# RPi_RFM12B_ISP_v1_1.net
KiCad netlist of a schematic drawn in EAGLE
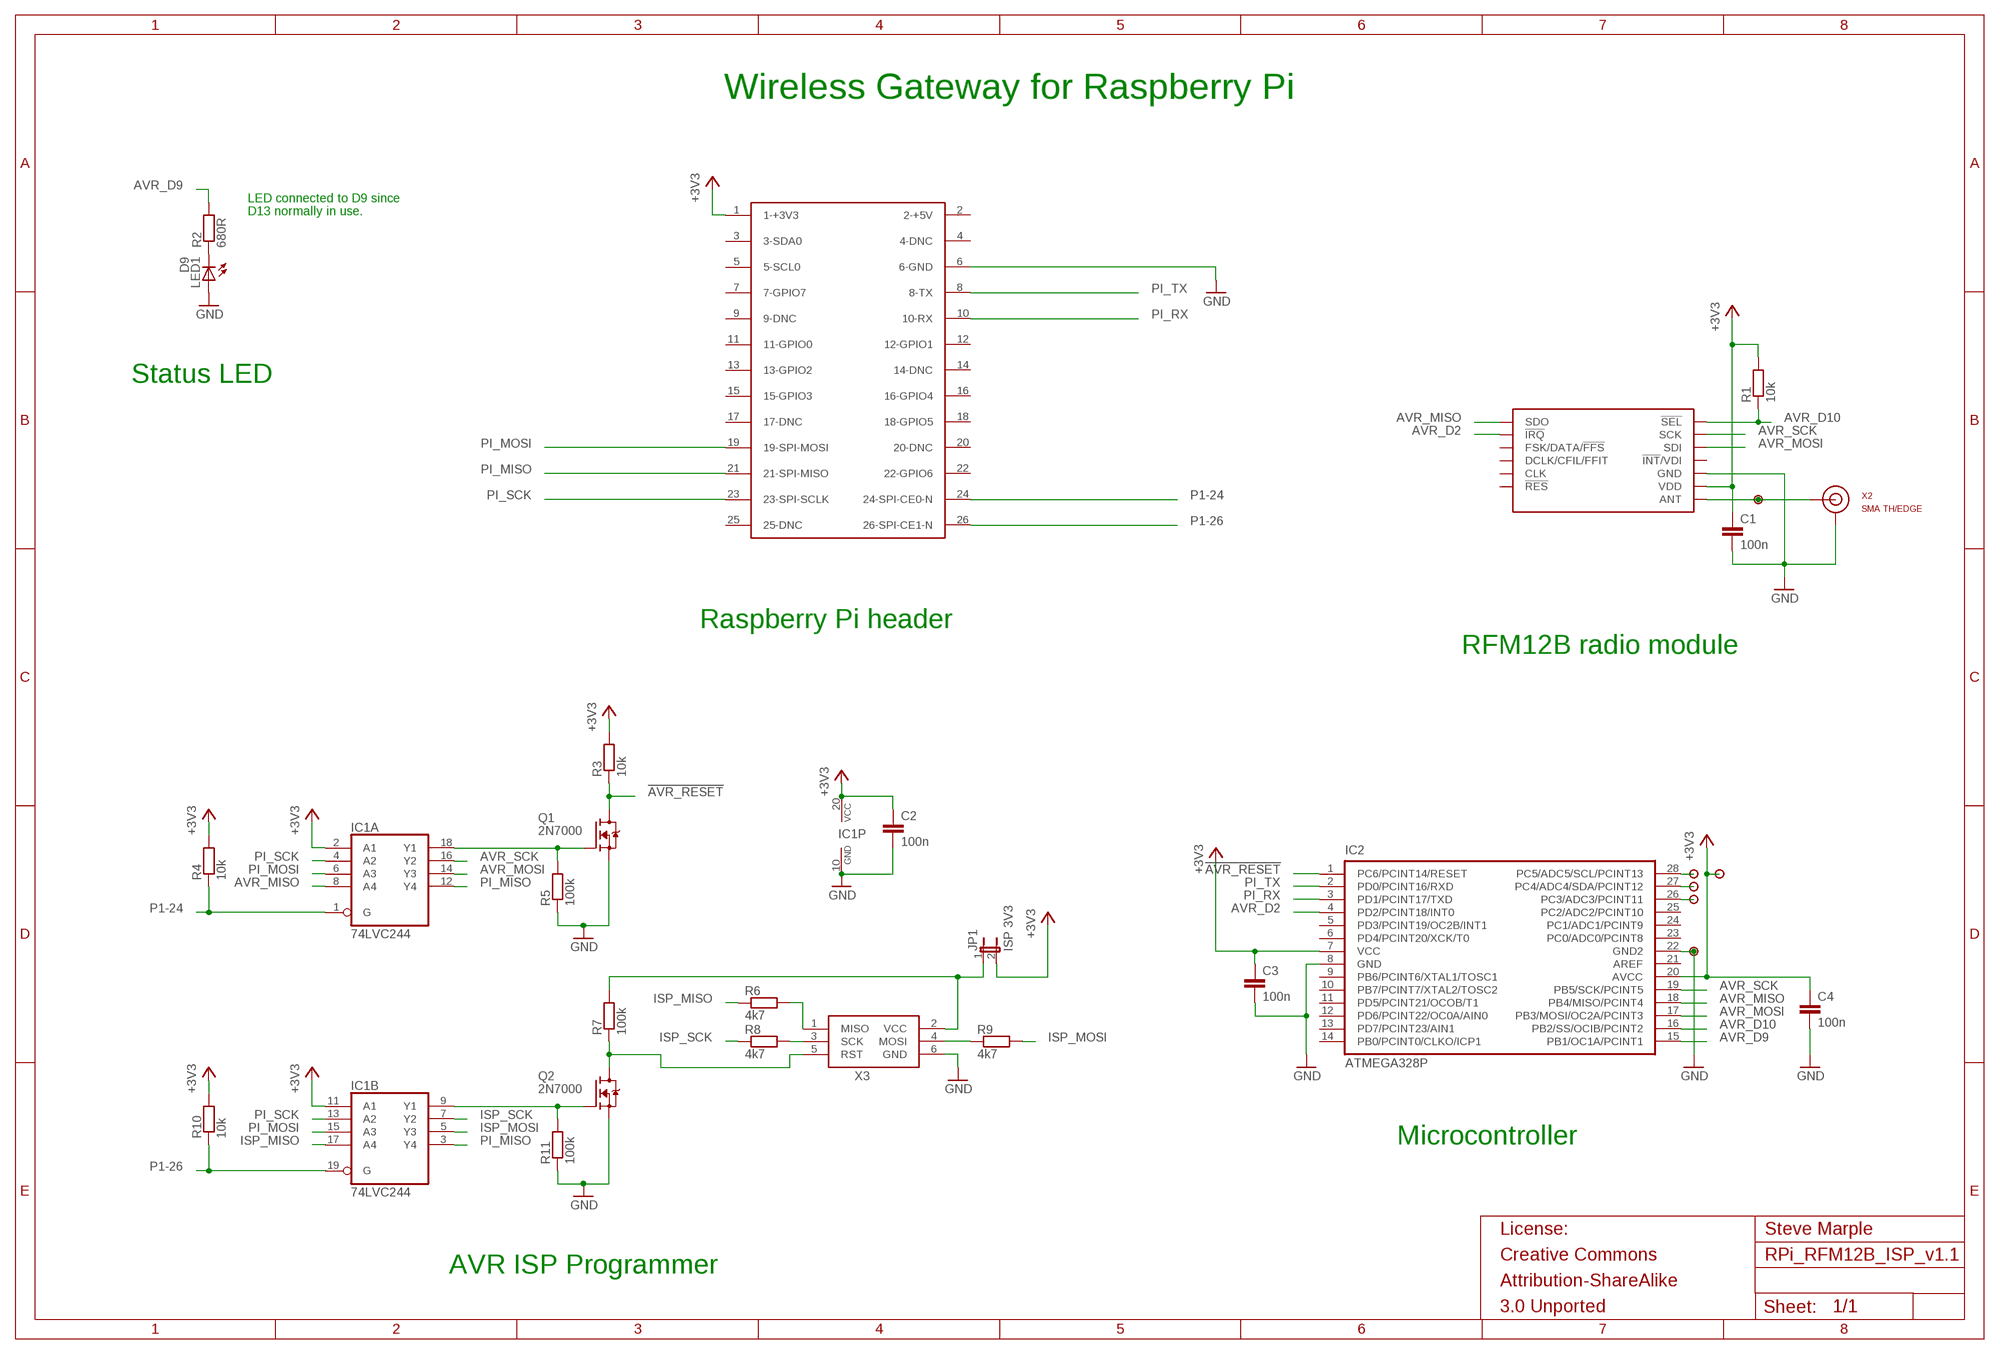
[diagram p0: schematic, sheet 1]

(export (version "E")
  (design (tool "Eeschema 10.0.6"))
  (components
    (comp (ref "AVR_A1")
      (value "PAD")
      (footprint "eagle-import:PAD")
      (libsource (lib "eagle-import") (part "PAD"))
    )
    (comp (ref "AVR_A2")
      (value "PAD")
      (footprint "eagle-import:PAD")
      (libsource (lib "eagle-import") (part "PAD"))
    )
    (comp (ref "AVR_A3")
      (value "PAD")
      (footprint "eagle-import:PAD")
      (libsource (lib "eagle-import") (part "PAD"))
    )
    (comp (ref "AVR_A4")
      (value "PAD")
      (footprint "eagle-import:PAD")
      (libsource (lib "eagle-import") (part "PAD"))
    )
    (comp (ref "AVR_A5")
      (value "PAD")
      (footprint "eagle-import:PAD")
      (libsource (lib "eagle-import") (part "PAD"))
    )
    (comp (ref "C1")
      (value "100n")
      (footprint "eagle-import:CAP-PTH-SMALL")
      (libsource (lib "eagle-import") (part "CAPPTH"))
    )
    (comp (ref "C2")
      (value "100n")
      (footprint "eagle-import:CAP-PTH-SMALL")
      (libsource (lib "eagle-import") (part "CAPPTH"))
    )
    (comp (ref "C3")
      (value "100n")
      (footprint "eagle-import:CAP-PTH-SMALL")
      (libsource (lib "eagle-import") (part "CAPPTH"))
    )
    (comp (ref "C4")
      (value "100n")
      (footprint "eagle-import:CAP-PTH-SMALL")
      (libsource (lib "eagle-import") (part "CAPPTH"))
    )
    (comp (ref "IC1")
      (value "74LVC244")
      (footprint "eagle-import:DIL20")
      (libsource (lib "eagle-import") (part "74244NHC"))
    )
    (comp (ref "IC2")
      (value "ATMEGA328P")
      (footprint "eagle-import:DIL28-N")
      (libsource (lib "eagle-import") (part "IC_UC_ATMEGA328PDIL"))
    )
    (comp (ref "JP1")
      (value "ISP 3V3")
      (footprint "eagle-import:1X02")
      (libsource (lib "eagle-import") (part "JUMPER-2PTH"))
    )
    (comp (ref "LED1")
      (value "D9")
      (footprint "eagle-import:LED3MM")
      (libsource (lib "eagle-import") (part "LED3MM"))
    )
    (comp (ref "Q1")
      (value "2N7000")
      (footprint "eagle-import:TO-92")
      (libsource (lib "eagle-import") (part "2N7000"))
    )
    (comp (ref "Q2")
      (value "2N7000")
      (footprint "eagle-import:TO-92")
      (libsource (lib "eagle-import") (part "2N7000"))
    )
    (comp (ref "R1")
      (value "10k")
      (footprint "eagle-import:RES-AXIAL-0.4")
      (libsource (lib "eagle-import") (part "RESISTOR"))
    )
    (comp (ref "R2")
      (value "680R")
      (footprint "eagle-import:RES-AXIAL-0.4")
      (libsource (lib "eagle-import") (part "RESISTOR"))
    )
    (comp (ref "R3")
      (value "10k")
      (footprint "eagle-import:RES-AXIAL-0.4")
      (libsource (lib "eagle-import") (part "RESISTOR"))
    )
    (comp (ref "R4")
      (value "10k")
      (footprint "eagle-import:RES-AXIAL-0.4")
      (libsource (lib "eagle-import") (part "RESISTOR"))
    )
    (comp (ref "R5")
      (value "100k")
      (footprint "eagle-import:RES-AXIAL-0.4")
      (libsource (lib "eagle-import") (part "RESISTOR"))
    )
    (comp (ref "R6")
      (value "4k7")
      (footprint "eagle-import:RES-AXIAL-0.4")
      (libsource (lib "eagle-import") (part "RESISTOR"))
    )
    (comp (ref "R7")
      (value "100k")
      (footprint "eagle-import:RES-AXIAL-0.4")
      (libsource (lib "eagle-import") (part "RESISTOR"))
    )
    (comp (ref "R8")
      (value "4k7")
      (footprint "eagle-import:RES-AXIAL-0.4")
      (libsource (lib "eagle-import") (part "RESISTOR"))
    )
    (comp (ref "R9")
      (value "4k7")
      (footprint "eagle-import:RES-AXIAL-0.4")
      (libsource (lib "eagle-import") (part "RESISTOR"))
    )
    (comp (ref "R10")
      (value "10k")
      (footprint "eagle-import:RES-AXIAL-0.4")
      (libsource (lib "eagle-import") (part "RESISTOR"))
    )
    (comp (ref "R11")
      (value "100k")
      (footprint "eagle-import:RES-AXIAL-0.4")
      (libsource (lib "eagle-import") (part "RESISTOR"))
    )
    (comp (ref "RF1")
      (value "RFM12B")
      (footprint "eagle-import:RFM12B")
      (libsource (lib "eagle-import") (part "RFM12BSMD"))
    )
    (comp (ref "RFM12B_ANT")
      (value "PAD")
      (footprint "eagle-import:PAD")
      (libsource (lib "eagle-import") (part "PAD"))
    )
    (comp (ref "X1")
      (value "P1A")
      (footprint "eagle-import:RASPBERRY-PI-HEADER")
      (libsource (lib "eagle-import") (part "RASPBERRY-PIHEADER"))
    )
    (comp (ref "X2")
      (value "SMA TH/EDGE")
      (footprint "eagle-import:SMA-THD-EDGE")
      (libsource (lib "eagle-import") (part "CONN-SMATHD-SMD-EDGE"))
    )
    (comp (ref "X3")
      (value "AVR ISP")
      (footprint "eagle-import:CONN-HARTING-ML6")
      (libsource (lib "eagle-import") (part "AVRISP-HEADER-6-SHROUDED"))
    )
  )
  (nets
    (net (code "1") (name "+3V3") (class "Default")
      (node (ref "AVR_A5") (pin "1") (pinfunction "1_1") (pintype "bidirectional"))
      (node (ref "C1") (pin "1") (pinfunction "1_1") (pintype "passive"))
      (node (ref "C2") (pin "1") (pinfunction "1_1") (pintype "passive"))
      (node (ref "C3") (pin "1") (pinfunction "1_1") (pintype "passive"))
      (node (ref "C4") (pin "1") (pinfunction "1_1") (pintype "passive"))
      (node (ref "IC1") (pin "11") (pinfunction "A1_11") (pintype "input"))
      (node (ref "IC1") (pin "2") (pinfunction "A1_2") (pintype "input"))
      (node (ref "IC1") (pin "20") (pinfunction "VCC_20") (pintype "power_in"))
      (node (ref "IC2") (pin "20") (pinfunction "AVCC_20") (pintype "bidirectional"))
      (node (ref "IC2") (pin "7") (pinfunction "VCC_7") (pintype "bidirectional"))
      (node (ref "JP1") (pin "2") (pinfunction "2_2") (pintype "passive"))
      (node (ref "R1") (pin "P$2") (pinfunction "2_P$2") (pintype "passive"))
      (node (ref "R10") (pin "P$2") (pinfunction "2_P$2") (pintype "passive"))
      (node (ref "R3") (pin "P$2") (pinfunction "2_P$2") (pintype "passive"))
      (node (ref "R4") (pin "P$2") (pinfunction "2_P$2") (pintype "passive"))
      (node (ref "RF1") (pin "VDD") (pinfunction "VDD_VDD") (pintype "power_in"))
      (node (ref "X1") (pin "1") (pinfunction "1-+3V3_1") (pintype "bidirectional"))
    )
    (net (code "2") (name "/AVR_D2") (class "Default")
      (node (ref "IC2") (pin "4") (pinfunction "PD2/PCINT18/INT0_4") (pintype "bidirectional"))
      (node (ref "RF1") (pin "!IRQ") (pinfunction "~{IRQ}_!IRQ") (pintype "output"))
    )
    (net (code "3") (name "/AVR_D9") (class "Default")
      (node (ref "IC2") (pin "15") (pinfunction "PB1/OC1A/PCINT1_15") (pintype "bidirectional"))
      (node (ref "R2") (pin "P$2") (pinfunction "2_P$2") (pintype "passive"))
    )
    (net (code "4") (name "/AVR_D10") (class "Default")
      (node (ref "IC2") (pin "16") (pinfunction "PB2/SS/OCIB/PCINT2_16") (pintype "bidirectional"))
      (node (ref "R1") (pin "P$1") (pinfunction "1_P$1") (pintype "passive"))
      (node (ref "RF1") (pin "!SEL") (pinfunction "~{SEL}_!SEL") (pintype "input"))
    )
    (net (code "5") (name "/AVR_MISO") (class "Default")
      (node (ref "IC1") (pin "8") (pinfunction "A4_8") (pintype "input"))
      (node (ref "IC2") (pin "18") (pinfunction "PB4/MISO/PCINT4_18") (pintype "bidirectional"))
      (node (ref "RF1") (pin "SDO") (pinfunction "SDO_SDO") (pintype "output"))
    )
    (net (code "6") (name "/AVR_MOSI") (class "Default")
      (node (ref "IC1") (pin "14") (pinfunction "Y3_14") (pintype "tri_state"))
      (node (ref "IC2") (pin "17") (pinfunction "PB3/MOSI/OC2A/PCINT3_17") (pintype "bidirectional"))
      (node (ref "RF1") (pin "SDI") (pinfunction "SDI_SDI") (pintype "input"))
    )
    (net (code "7") (name "/AVR_SCK") (class "Default")
      (node (ref "IC1") (pin "16") (pinfunction "Y2_16") (pintype "tri_state"))
      (node (ref "IC2") (pin "19") (pinfunction "PB5/SCK/PCINT5_19") (pintype "bidirectional"))
      (node (ref "RF1") (pin "SCK") (pinfunction "SCK_SCK") (pintype "input"))
    )
    (net (code "8") (name "/ISP_MISO") (class "Default")
      (node (ref "IC1") (pin "17") (pinfunction "A4_17") (pintype "input"))
      (node (ref "R6") (pin "P$1") (pinfunction "1_P$1") (pintype "passive"))
    )
    (net (code "9") (name "/ISP_MOSI") (class "Default")
      (node (ref "IC1") (pin "5") (pinfunction "Y3_5") (pintype "tri_state"))
      (node (ref "R9") (pin "P$2") (pinfunction "2_P$2") (pintype "passive"))
    )
    (net (code "10") (name "/ISP_SCK") (class "Default")
      (node (ref "IC1") (pin "7") (pinfunction "Y2_7") (pintype "tri_state"))
      (node (ref "R8") (pin "P$1") (pinfunction "1_P$1") (pintype "passive"))
    )
    (net (code "11") (name "/P1-24") (class "Default")
      (node (ref "IC1") (pin "1") (pinfunction "G_1") (pintype "input"))
      (node (ref "R4") (pin "P$1") (pinfunction "1_P$1") (pintype "passive"))
      (node (ref "X1") (pin "24") (pinfunction "24-SPI-CE0-N_24") (pintype "bidirectional"))
    )
    (net (code "12") (name "/P1-26") (class "Default")
      (node (ref "IC1") (pin "19") (pinfunction "G_19") (pintype "input"))
      (node (ref "R10") (pin "P$1") (pinfunction "1_P$1") (pintype "passive"))
      (node (ref "X1") (pin "26") (pinfunction "26-SPI-CE1-N_26") (pintype "bidirectional"))
    )
    (net (code "13") (name "/PI_MISO") (class "Default")
      (node (ref "IC1") (pin "12") (pinfunction "Y4_12") (pintype "tri_state"))
      (node (ref "IC1") (pin "3") (pinfunction "Y4_3") (pintype "tri_state"))
      (node (ref "X1") (pin "21") (pinfunction "21-SPI-MISO_21") (pintype "bidirectional"))
    )
    (net (code "14") (name "/PI_MOSI") (class "Default")
      (node (ref "IC1") (pin "15") (pinfunction "A3_15") (pintype "input"))
      (node (ref "IC1") (pin "6") (pinfunction "A3_6") (pintype "input"))
      (node (ref "X1") (pin "19") (pinfunction "19-SPI-MOSI_19") (pintype "bidirectional"))
    )
    (net (code "15") (name "/PI_RX") (class "Default")
      (node (ref "IC2") (pin "3") (pinfunction "PD1/PCINT17/TXD_3") (pintype "bidirectional"))
      (node (ref "X1") (pin "10") (pinfunction "10-RX_10") (pintype "bidirectional"))
    )
    (net (code "16") (name "/PI_SCK") (class "Default")
      (node (ref "IC1") (pin "13") (pinfunction "A2_13") (pintype "input"))
      (node (ref "IC1") (pin "4") (pinfunction "A2_4") (pintype "input"))
      (node (ref "X1") (pin "23") (pinfunction "23-SPI-SCLK_23") (pintype "bidirectional"))
    )
    (net (code "17") (name "/PI_TX") (class "Default")
      (node (ref "IC2") (pin "2") (pinfunction "PD0/PCINT16/RXD_2") (pintype "bidirectional"))
      (node (ref "X1") (pin "8") (pinfunction "8-TX_8") (pintype "bidirectional"))
    )
    (net (code "18") (name "/~{AVR_RESET}") (class "Default")
      (node (ref "IC2") (pin "1") (pinfunction "PC6/PCINT14/RESET_1") (pintype "bidirectional"))
      (node (ref "Q1") (pin "3") (pinfunction "D_3") (pintype "passive"))
      (node (ref "R3") (pin "P$1") (pinfunction "1_P$1") (pintype "passive"))
    )
    (net (code "19") (name "GND") (class "Default")
      (node (ref "AVR_A4") (pin "1") (pinfunction "1_1") (pintype "bidirectional"))
      (node (ref "C1") (pin "2") (pinfunction "2_2") (pintype "passive"))
      (node (ref "C2") (pin "2") (pinfunction "2_2") (pintype "passive"))
      (node (ref "C3") (pin "2") (pinfunction "2_2") (pintype "passive"))
      (node (ref "C4") (pin "2") (pinfunction "2_2") (pintype "passive"))
      (node (ref "IC1") (pin "10") (pinfunction "GND_10") (pintype "power_in"))
      (node (ref "IC2") (pin "22") (pinfunction "GND2_22") (pintype "bidirectional"))
      (node (ref "IC2") (pin "8") (pinfunction "GND_8") (pintype "bidirectional"))
      (node (ref "LED1") (pin "A") (pinfunction "A_A") (pintype "passive"))
      (node (ref "Q1") (pin "1") (pinfunction "S_1") (pintype "passive"))
      (node (ref "Q2") (pin "1") (pinfunction "S_1") (pintype "passive"))
      (node (ref "R11") (pin "P$1") (pinfunction "1_P$1") (pintype "passive"))
      (node (ref "R5") (pin "P$1") (pinfunction "1_P$1") (pintype "passive"))
      (node (ref "RF1") (pin "GND@0") (pinfunction "GND_GND@0") (pintype "power_in"))
      (node (ref "RF1") (pin "GND@1") (pinfunction "GND_GND@1") (pintype "power_in"))
      (node (ref "X1") (pin "6") (pinfunction "6-GND_6") (pintype "bidirectional"))
      (node (ref "X2") (pin "GND@0") (pinfunction "GND_GND@0") (pintype "bidirectional"))
      (node (ref "X2") (pin "GND@1") (pinfunction "GND_GND@1") (pintype "bidirectional"))
      (node (ref "X2") (pin "GND@2") (pinfunction "GND_GND@2") (pintype "bidirectional"))
      (node (ref "X2") (pin "GND@3") (pinfunction "GND_GND@3") (pintype "bidirectional"))
      (node (ref "X2") (pin "GND@EDGE0") (pinfunction "GND_GND@EDGE0") (pintype "bidirectional"))
      (node (ref "X2") (pin "GND@EDGE1") (pinfunction "GND_GND@EDGE1") (pintype "bidirectional"))
      (node (ref "X2") (pin "GND@EDGE2") (pinfunction "GND_GND@EDGE2") (pintype "bidirectional"))
      (node (ref "X2") (pin "GND@EDGE3") (pinfunction "GND_GND@EDGE3") (pintype "bidirectional"))
      (node (ref "X3") (pin "6") (pinfunction "GND_6") (pintype "power_in"))
    )
    (net (code "20") (name "Net-(IC1A-Y1)") (class "Default")
      (node (ref "IC1") (pin "18") (pinfunction "Y1_18") (pintype "tri_state"))
      (node (ref "Q1") (pin "2") (pinfunction "G_2") (pintype "passive"))
      (node (ref "R5") (pin "P$2") (pinfunction "2_P$2") (pintype "passive"))
    )
    (net (code "21") (name "Net-(IC1B-Y1)") (class "Default")
      (node (ref "IC1") (pin "9") (pinfunction "Y1_9") (pintype "tri_state"))
      (node (ref "Q2") (pin "2") (pinfunction "G_2") (pintype "passive"))
      (node (ref "R11") (pin "P$2") (pinfunction "2_P$2") (pintype "passive"))
    )
    (net (code "22") (name "Net-(IC2-PC3{slash}ADC3{slash}PCINT11)") (class "Default")
      (node (ref "AVR_A3") (pin "1") (pinfunction "1_1") (pintype "bidirectional"))
      (node (ref "IC2") (pin "26") (pinfunction "PC3/ADC3/PCINT11_26") (pintype "bidirectional"))
    )
    (net (code "23") (name "Net-(IC2-PC4{slash}ADC4{slash}SDA{slash}PCINT12)") (class "Default")
      (node (ref "AVR_A2") (pin "1") (pinfunction "1_1") (pintype "bidirectional"))
      (node (ref "IC2") (pin "27") (pinfunction "PC4/ADC4/SDA/PCINT12_27") (pintype "bidirectional"))
    )
    (net (code "24") (name "Net-(IC2-PC5{slash}ADC5{slash}SCL{slash}PCINT13)") (class "Default")
      (node (ref "AVR_A1") (pin "1") (pinfunction "1_1") (pintype "bidirectional"))
      (node (ref "IC2") (pin "28") (pinfunction "PC5/ADC5/SCL/PCINT13_28") (pintype "bidirectional"))
    )
    (net (code "25") (name "Net-(LED1-C)") (class "Default")
      (node (ref "LED1") (pin "K") (pinfunction "C_K") (pintype "passive"))
      (node (ref "R2") (pin "P$1") (pinfunction "1_P$1") (pintype "passive"))
    )
    (net (code "26") (name "Net-(Q2-D)") (class "Default")
      (node (ref "Q2") (pin "3") (pinfunction "D_3") (pintype "passive"))
      (node (ref "R7") (pin "P$1") (pinfunction "1_P$1") (pintype "passive"))
      (node (ref "X3") (pin "5") (pinfunction "RST_5") (pintype "bidirectional"))
    )
    (net (code "27") (name "Net-(R6-2)") (class "Default")
      (node (ref "R6") (pin "P$2") (pinfunction "2_P$2") (pintype "passive"))
      (node (ref "X3") (pin "1") (pinfunction "MISO_1") (pintype "bidirectional"))
    )
    (net (code "28") (name "Net-(R7-2)") (class "Default")
      (node (ref "JP1") (pin "1") (pinfunction "1_1") (pintype "passive"))
      (node (ref "R7") (pin "P$2") (pinfunction "2_P$2") (pintype "passive"))
      (node (ref "X3") (pin "2") (pinfunction "VCC_2") (pintype "power_in"))
    )
    (net (code "29") (name "Net-(R8-2)") (class "Default")
      (node (ref "R8") (pin "P$2") (pinfunction "2_P$2") (pintype "passive"))
      (node (ref "X3") (pin "3") (pinfunction "SCK_3") (pintype "bidirectional"))
    )
    (net (code "30") (name "Net-(R9-1)") (class "Default")
      (node (ref "R9") (pin "P$1") (pinfunction "1_P$1") (pintype "passive"))
      (node (ref "X3") (pin "4") (pinfunction "MOSI_4") (pintype "bidirectional"))
    )
    (net (code "31") (name "Net-(RF1-PadANT)") (class "Default")
      (node (ref "RF1") (pin "ANT") (pinfunction "ANT_ANT") (pintype "passive"))
      (node (ref "RFM12B_ANT") (pin "1") (pinfunction "1_1") (pintype "bidirectional"))
      (node (ref "X2") (pin "SIG") (pinfunction "SIGNAL_SIG") (pintype "bidirectional"))
      (node (ref "X2") (pin "SIG@EDGE") (pinfunction "SIGNAL_SIG@EDGE") (pintype "bidirectional"))
    )
    (net (code "32") (name "unconnected-(IC2-AREF-Pad21)") (class "Default")
      (node (ref "IC2") (pin "21") (pinfunction "AREF_21") (pintype "bidirectional"))
    )
    (net (code "33") (name "unconnected-(IC2-PB0{slash}PCINT0{slash}CLKO{slash}ICP1-Pad14)") (class "Default")
      (node (ref "IC2") (pin "14") (pinfunction "PB0/PCINT0/CLKO/ICP1_14") (pintype "bidirectional"))
    )
    (net (code "34") (name "unconnected-(IC2-PB6{slash}PCINT6{slash}XTAL1{slash}TOSC1-Pad9)") (class "Default")
      (node (ref "IC2") (pin "9") (pinfunction "PB6/PCINT6/XTAL1/TOSC1_9") (pintype "bidirectional"))
    )
    (net (code "35") (name "unconnected-(IC2-PB7{slash}PCINT7{slash}XTAL2{slash}TOSC2-Pad10)") (class "Default")
      (node (ref "IC2") (pin "10") (pinfunction "PB7/PCINT7/XTAL2/TOSC2_10") (pintype "bidirectional"))
    )
    (net (code "36") (name "unconnected-(IC2-PC0{slash}ADC0{slash}PCINT8-Pad23)") (class "Default")
      (node (ref "IC2") (pin "23") (pinfunction "PC0/ADC0/PCINT8_23") (pintype "bidirectional"))
    )
    (net (code "37") (name "unconnected-(IC2-PC1{slash}ADC1{slash}PCINT9-Pad24)") (class "Default")
      (node (ref "IC2") (pin "24") (pinfunction "PC1/ADC1/PCINT9_24") (pintype "bidirectional"))
    )
    (net (code "38") (name "unconnected-(IC2-PC2{slash}ADC2{slash}PCINT10-Pad25)") (class "Default")
      (node (ref "IC2") (pin "25") (pinfunction "PC2/ADC2/PCINT10_25") (pintype "bidirectional"))
    )
    (net (code "39") (name "unconnected-(IC2-PD3{slash}PCINT19{slash}OC2B{slash}INT1-Pad5)") (class "Default")
      (node (ref "IC2") (pin "5") (pinfunction "PD3/PCINT19/OC2B/INT1_5") (pintype "bidirectional"))
    )
    (net (code "40") (name "unconnected-(IC2-PD4{slash}PCINT20{slash}XCK{slash}T0-Pad6)") (class "Default")
      (node (ref "IC2") (pin "6") (pinfunction "PD4/PCINT20/XCK/T0_6") (pintype "bidirectional"))
    )
    (net (code "41") (name "unconnected-(IC2-PD5{slash}PCINT21{slash}OCOB{slash}T1-Pad11)") (class "Default")
      (node (ref "IC2") (pin "11") (pinfunction "PD5/PCINT21/OCOB/T1_11") (pintype "bidirectional"))
    )
    (net (code "42") (name "unconnected-(IC2-PD6{slash}PCINT22{slash}OC0A{slash}AIN0-Pad12)") (class "Default")
      (node (ref "IC2") (pin "12") (pinfunction "PD6/PCINT22/OC0A/AIN0_12") (pintype "bidirectional"))
    )
    (net (code "43") (name "unconnected-(IC2-PD7{slash}PCINT23{slash}AIN1-Pad13)") (class "Default")
      (node (ref "IC2") (pin "13") (pinfunction "PD7/PCINT23/AIN1_13") (pintype "bidirectional"))
    )
    (net (code "44") (name "unconnected-(RF1-FSK{slash}DATA{slash}~{FFS}-PadFSK{slash}DATA{slash}!FFS)") (class "Default")
      (node (ref "RF1") (pin "FSK/DATA/!FFS") (pinfunction "FSK/DATA/~{FFS}_FSK/DATA/!FFS") (pintype "bidirectional"))
    )
    (net (code "45") (name "unconnected-(RF1-PadCLK)") (class "Default")
      (node (ref "RF1") (pin "CLK") (pinfunction "CLK_CLK") (pintype "output"))
    )
    (net (code "46") (name "unconnected-(RF1-PadDCLK{slash}CFIL{slash}FFIT)") (class "Default")
      (node (ref "RF1") (pin "DCLK/CFIL/FFIT") (pinfunction "DCLK/CFIL/FFIT_DCLK/CFIL/FFIT") (pintype "bidirectional"))
    )
    (net (code "47") (name "unconnected-(RF1-~{INT}{slash}VDI-Pad!INT!{slash}VDI)") (class "Default")
      (node (ref "RF1") (pin "!INT!/VDI") (pinfunction "~{INT}/VDI_!INT!/VDI") (pintype "bidirectional"))
    )
    (net (code "48") (name "unconnected-(RF1-~{RES}-Pad!RES)") (class "Default")
      (node (ref "RF1") (pin "!RES") (pinfunction "~{RES}_!RES") (pintype "bidirectional"))
    )
    (net (code "49") (name "unconnected-(X1-2-+5V-Pad2)") (class "Default")
      (node (ref "X1") (pin "2") (pinfunction "2-+5V_2") (pintype "bidirectional"))
    )
    (net (code "50") (name "unconnected-(X1-3-SDA0-Pad3)") (class "Default")
      (node (ref "X1") (pin "3") (pinfunction "3-SDA0_3") (pintype "bidirectional"))
    )
    (net (code "51") (name "unconnected-(X1-4-DNC-Pad4)") (class "Default")
      (node (ref "X1") (pin "4") (pinfunction "4-DNC_4") (pintype "bidirectional"))
    )
    (net (code "52") (name "unconnected-(X1-5-SCL0-Pad5)") (class "Default")
      (node (ref "X1") (pin "5") (pinfunction "5-SCL0_5") (pintype "bidirectional"))
    )
    (net (code "53") (name "unconnected-(X1-7-GPIO7-Pad7)") (class "Default")
      (node (ref "X1") (pin "7") (pinfunction "7-GPIO7_7") (pintype "bidirectional"))
    )
    (net (code "54") (name "unconnected-(X1-9-DNC-Pad9)") (class "Default")
      (node (ref "X1") (pin "9") (pinfunction "9-DNC_9") (pintype "bidirectional"))
    )
    (net (code "55") (name "unconnected-(X1-11-GPIO0-Pad11)") (class "Default")
      (node (ref "X1") (pin "11") (pinfunction "11-GPIO0_11") (pintype "bidirectional"))
    )
    (net (code "56") (name "unconnected-(X1-12-GPIO1-Pad12)") (class "Default")
      (node (ref "X1") (pin "12") (pinfunction "12-GPIO1_12") (pintype "bidirectional"))
    )
    (net (code "57") (name "unconnected-(X1-13-GPIO2-Pad13)") (class "Default")
      (node (ref "X1") (pin "13") (pinfunction "13-GPIO2_13") (pintype "bidirectional"))
    )
    (net (code "58") (name "unconnected-(X1-14-DNC-Pad14)") (class "Default")
      (node (ref "X1") (pin "14") (pinfunction "14-DNC_14") (pintype "bidirectional"))
    )
    (net (code "59") (name "unconnected-(X1-15-GPIO3-Pad15)") (class "Default")
      (node (ref "X1") (pin "15") (pinfunction "15-GPIO3_15") (pintype "bidirectional"))
    )
    (net (code "60") (name "unconnected-(X1-16-GPIO4-Pad16)") (class "Default")
      (node (ref "X1") (pin "16") (pinfunction "16-GPIO4_16") (pintype "bidirectional"))
    )
    (net (code "61") (name "unconnected-(X1-17-DNC-Pad17)") (class "Default")
      (node (ref "X1") (pin "17") (pinfunction "17-DNC_17") (pintype "bidirectional"))
    )
    (net (code "62") (name "unconnected-(X1-18-GPIO5-Pad18)") (class "Default")
      (node (ref "X1") (pin "18") (pinfunction "18-GPIO5_18") (pintype "bidirectional"))
    )
    (net (code "63") (name "unconnected-(X1-20-DNC-Pad20)") (class "Default")
      (node (ref "X1") (pin "20") (pinfunction "20-DNC_20") (pintype "bidirectional"))
    )
    (net (code "64") (name "unconnected-(X1-22-GPIO6-Pad22)") (class "Default")
      (node (ref "X1") (pin "22") (pinfunction "22-GPIO6_22") (pintype "bidirectional"))
    )
    (net (code "65") (name "unconnected-(X1-25-DNC-Pad25)") (class "Default")
      (node (ref "X1") (pin "25") (pinfunction "25-DNC_25") (pintype "bidirectional"))
    )
  )
)
